# MOTORS.net
KiCad netlist of a schematic drawn in Altium Designer
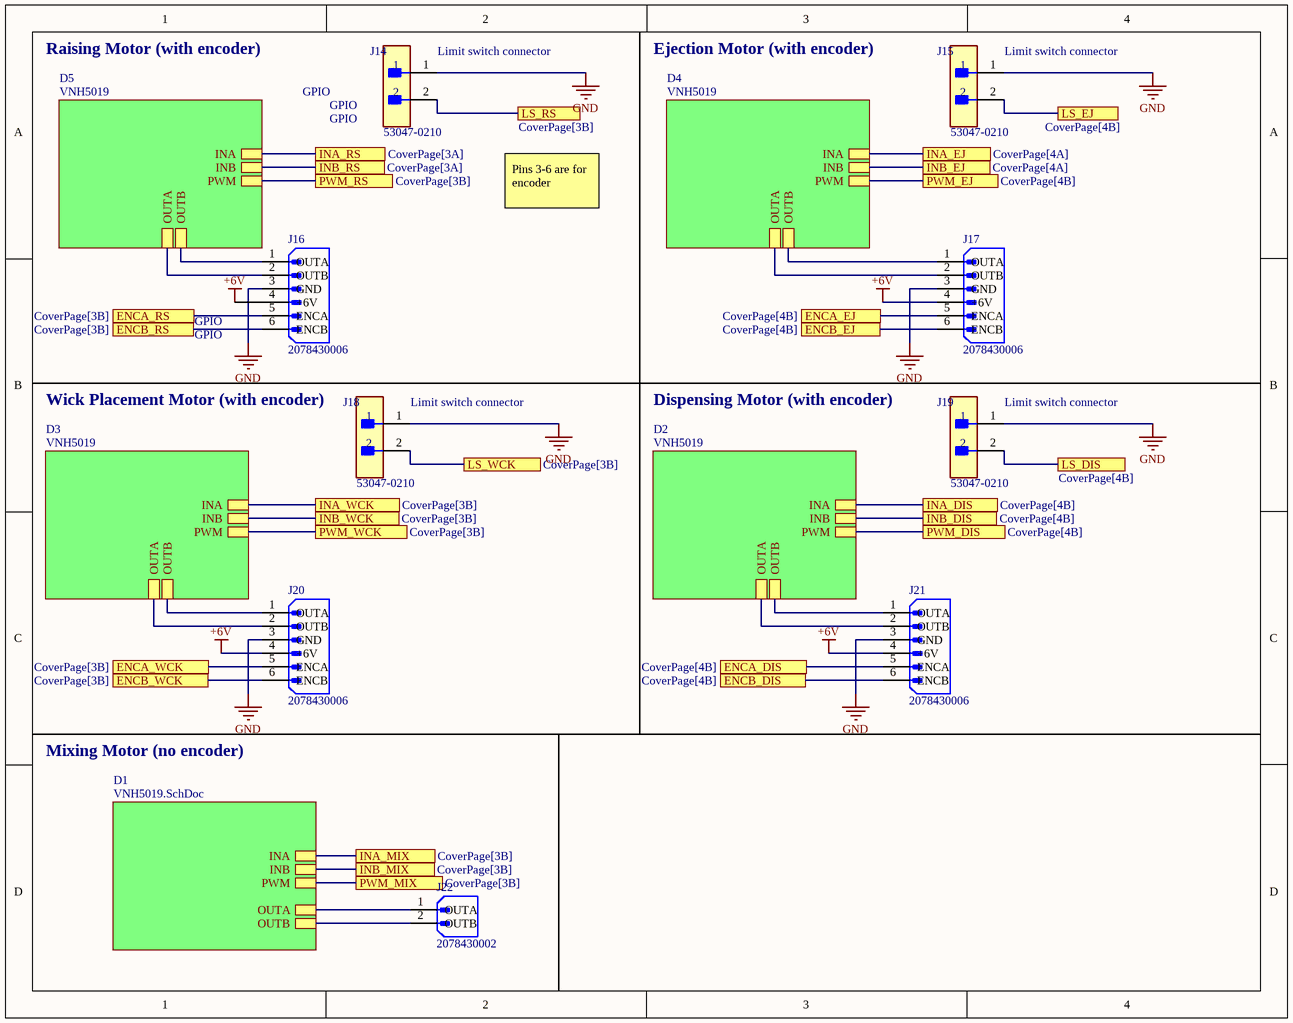
[diagram p0: MOTORS.SchDoc]

(export (version "E")
  (design (tool "Eeschema 10.0.6"))
  (components
    (comp (ref "J14")
      (value "53047-0210")
      (footprint "FP-53047-0210-MFG")
      (description "CONN HEADER VERT 2POS 1.25MM")
      (fields
        (field (name "OCTOPART") "https://octopart.com/53047-0210-molex-276772")
        (field (name "MANUFACTURER") "Molex")
      )
      (libsource (lib "Altium Content Vault") (part "3bc925449376181038e59eaffc5286c"))
    )
    (comp (ref "J15")
      (value "53047-0210")
      (footprint "FP-53047-0210-MFG")
      (description "CONN HEADER VERT 2POS 1.25MM")
      (fields
        (field (name "OCTOPART") "https://octopart.com/53047-0210-molex-276772")
        (field (name "MANUFACTURER") "Molex")
      )
      (libsource (lib "Altium Content Vault") (part "3bc925449376181038e59eaffc5286c"))
    )
    (comp (ref "J16")
      (value "2078430006")
      (footprint "MOLEX_2078430006")
      (libsource (lib "Northeastern University - Generate") (part "2078430006"))
    )
    (comp (ref "J17")
      (value "2078430006")
      (footprint "MOLEX_2078430006")
      (libsource (lib "Northeastern University - Generate") (part "2078430006"))
    )
    (comp (ref "J18")
      (value "53047-0210")
      (footprint "FP-53047-0210-MFG")
      (description "CONN HEADER VERT 2POS 1.25MM")
      (fields
        (field (name "OCTOPART") "https://octopart.com/53047-0210-molex-276772")
        (field (name "MANUFACTURER") "Molex")
      )
      (libsource (lib "Altium Content Vault") (part "3bc925449376181038e59eaffc5286c"))
    )
    (comp (ref "J19")
      (value "53047-0210")
      (footprint "FP-53047-0210-MFG")
      (description "CONN HEADER VERT 2POS 1.25MM")
      (fields
        (field (name "OCTOPART") "https://octopart.com/53047-0210-molex-276772")
        (field (name "MANUFACTURER") "Molex")
      )
      (libsource (lib "Altium Content Vault") (part "3bc925449376181038e59eaffc5286c"))
    )
    (comp (ref "J20")
      (value "2078430006")
      (footprint "MOLEX_2078430006")
      (libsource (lib "Northeastern University - Generate") (part "2078430006"))
    )
    (comp (ref "J21")
      (value "2078430006")
      (footprint "MOLEX_2078430006")
      (libsource (lib "Northeastern University - Generate") (part "2078430006"))
    )
    (comp (ref "J22")
      (value "2078430002")
      (footprint "MOLEX_2078430002")
      (description "Conn Wire to Board HDR 6 POS 2.5mm Solder ST Top Entry Thru-Hole Bag")
      (fields (field (name "MF") "Molex"))
      (libsource (lib "Northeastern University - Generate") (part "2078430002"))
    )
  )
  (nets
    (net (code "1") (name "+6V") (class "Default")
      (node (ref "J16") (pin "4") (pinfunction "+6V_4") (pintype "passive"))
      (node (ref "J17") (pin "4") (pinfunction "+6V_4") (pintype "passive"))
      (node (ref "J20") (pin "4") (pinfunction "+6V_4") (pintype "passive"))
      (node (ref "J21") (pin "4") (pinfunction "+6V_4") (pintype "passive"))
    )
    (net (code "2") (name "/ENCA_DIS") (class "Default")
      (node (ref "J21") (pin "5") (pinfunction "ENCA_5") (pintype "passive"))
    )
    (net (code "3") (name "/ENCA_EJ") (class "Default")
      (node (ref "J17") (pin "5") (pinfunction "ENCA_5") (pintype "passive"))
    )
    (net (code "4") (name "/ENCA_RS") (class "Default")
      (node (ref "J16") (pin "5") (pinfunction "ENCA_5") (pintype "passive"))
    )
    (net (code "5") (name "/ENCA_WCK") (class "Default")
      (node (ref "J20") (pin "5") (pinfunction "ENCA_5") (pintype "passive"))
    )
    (net (code "6") (name "/ENCB_DIS") (class "Default")
      (node (ref "J21") (pin "6") (pinfunction "ENCB_6") (pintype "passive"))
    )
    (net (code "7") (name "/ENCB_EJ") (class "Default")
      (node (ref "J17") (pin "6") (pinfunction "ENCB_6") (pintype "passive"))
    )
    (net (code "8") (name "/ENCB_RS") (class "Default")
      (node (ref "J16") (pin "6") (pinfunction "ENCB_6") (pintype "passive"))
    )
    (net (code "9") (name "/ENCB_WCK") (class "Default")
      (node (ref "J20") (pin "6") (pinfunction "ENCB_6") (pintype "passive"))
    )
    (net (code "20") (name "/LS_DIS") (class "Default")
      (node (ref "J19") (pin "2") (pinfunction "2_2") (pintype "passive"))
    )
    (net (code "21") (name "/LS_EJ") (class "Default")
      (node (ref "J15") (pin "2") (pinfunction "2_2") (pintype "passive"))
    )
    (net (code "22") (name "/LS_RS") (class "Default")
      (node (ref "J14") (pin "2") (pinfunction "2_2") (pintype "passive"))
    )
    (net (code "23") (name "/LS_WCK") (class "Default")
      (node (ref "J18") (pin "2") (pinfunction "2_2") (pintype "passive"))
    )
    (net (code "24") (name "/OUTA") (class "Default")
      (node (ref "J17") (pin "2") (pinfunction "OUTB_2") (pintype "passive"))
    )
    (net (code "25") (name "/OUTA_1") (class "Default")
      (node (ref "J16") (pin "2") (pinfunction "OUTB_2") (pintype "passive"))
    )
    (net (code "26") (name "/OUTA_2") (class "Default")
      (node (ref "J20") (pin "2") (pinfunction "OUTB_2") (pintype "passive"))
    )
    (net (code "27") (name "/OUTA_3") (class "Default")
      (node (ref "J22") (pin "1") (pinfunction "OUTA_1") (pintype "passive"))
    )
    (net (code "28") (name "/OUTA_4") (class "Default")
      (node (ref "J21") (pin "2") (pinfunction "OUTB_2") (pintype "passive"))
    )
    (net (code "29") (name "/OUTB") (class "Default")
      (node (ref "J21") (pin "1") (pinfunction "OUTA_1") (pintype "passive"))
    )
    (net (code "30") (name "/OUTB_1") (class "Default")
      (node (ref "J16") (pin "1") (pinfunction "OUTA_1") (pintype "passive"))
    )
    (net (code "31") (name "/OUTB_2") (class "Default")
      (node (ref "J20") (pin "1") (pinfunction "OUTA_1") (pintype "passive"))
    )
    (net (code "32") (name "/OUTB_3") (class "Default")
      (node (ref "J22") (pin "2") (pinfunction "OUTB_2") (pintype "passive"))
    )
    (net (code "33") (name "/OUTB_4") (class "Default")
      (node (ref "J17") (pin "1") (pinfunction "OUTA_1") (pintype "passive"))
    )
    (net (code "39") (name "GND") (class "Default")
      (node (ref "J14") (pin "1") (pinfunction "1_1") (pintype "passive"))
      (node (ref "J15") (pin "1") (pinfunction "1_1") (pintype "passive"))
      (node (ref "J16") (pin "3") (pinfunction "GND_3") (pintype "passive"))
      (node (ref "J17") (pin "3") (pinfunction "GND_3") (pintype "passive"))
      (node (ref "J18") (pin "1") (pinfunction "1_1") (pintype "passive"))
      (node (ref "J19") (pin "1") (pinfunction "1_1") (pintype "passive"))
      (node (ref "J20") (pin "3") (pinfunction "GND_3") (pintype "passive"))
      (node (ref "J21") (pin "3") (pinfunction "GND_3") (pintype "passive"))
    )
  )
)
